# bwrev4.net
KiCad netlist of a schematic drawn in EAGLE
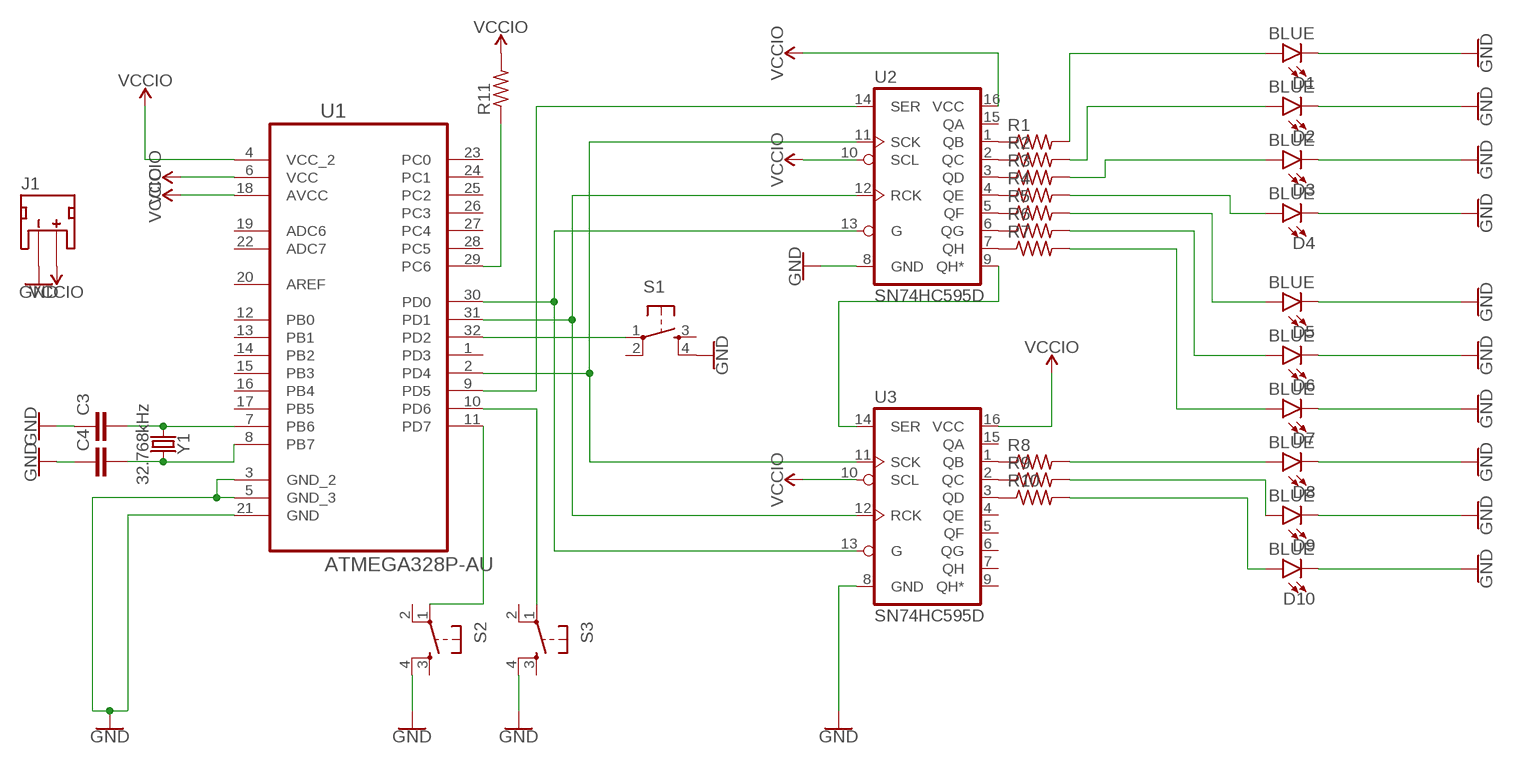
[diagram p0: schematic, sheet 1]

(export (version "E")
  (design (tool "Eeschema 10.0.6"))
  (components
    (comp (ref "C3")
      (value "C-EUC0805")
      (footprint "eagle-import:C0805")
      (libsource (lib "eagle-import") (part "C-EUC0805"))
    )
    (comp (ref "C4")
      (value "C-EUC0805")
      (footprint "eagle-import:C0805")
      (libsource (lib "eagle-import") (part "C-EUC0805"))
    )
    (comp (ref "D1")
      (value "BLUE")
      (footprint "eagle-import:LED-1206")
      (libsource (lib "eagle-import") (part "LED-BLUE1206"))
    )
    (comp (ref "D2")
      (value "BLUE")
      (footprint "eagle-import:LED-1206")
      (libsource (lib "eagle-import") (part "LED-BLUE1206"))
    )
    (comp (ref "D3")
      (value "BLUE")
      (footprint "eagle-import:LED-1206")
      (libsource (lib "eagle-import") (part "LED-BLUE1206"))
    )
    (comp (ref "D4")
      (value "BLUE")
      (footprint "eagle-import:LED-1206")
      (libsource (lib "eagle-import") (part "LED-BLUE1206"))
    )
    (comp (ref "D5")
      (value "BLUE")
      (footprint "eagle-import:LED-1206")
      (libsource (lib "eagle-import") (part "LED-BLUE1206"))
    )
    (comp (ref "D6")
      (value "BLUE")
      (footprint "eagle-import:LED-1206")
      (libsource (lib "eagle-import") (part "LED-BLUE1206"))
    )
    (comp (ref "D7")
      (value "BLUE")
      (footprint "eagle-import:LED-1206")
      (libsource (lib "eagle-import") (part "LED-BLUE1206"))
    )
    (comp (ref "D8")
      (value "BLUE")
      (footprint "eagle-import:LED-1206")
      (libsource (lib "eagle-import") (part "LED-BLUE1206"))
    )
    (comp (ref "D9")
      (value "BLUE")
      (footprint "eagle-import:LED-1206")
      (libsource (lib "eagle-import") (part "LED-BLUE1206"))
    )
    (comp (ref "D10")
      (value "BLUE")
      (footprint "eagle-import:LED-1206")
      (libsource (lib "eagle-import") (part "LED-BLUE1206"))
    )
    (comp (ref "J1")
      (value "JST_2MM_MALE")
      (footprint "eagle-import:JST-2-SMD")
      (libsource (lib "eagle-import") (part "JST_2MM_MALE"))
    )
    (comp (ref "R1")
      (value "R-US_M0805")
      (footprint "eagle-import:M0805")
      (libsource (lib "eagle-import") (part "R-US_M0805"))
    )
    (comp (ref "R2")
      (value "R-US_M0805")
      (footprint "eagle-import:M0805")
      (libsource (lib "eagle-import") (part "R-US_M0805"))
    )
    (comp (ref "R3")
      (value "R-US_M0805")
      (footprint "eagle-import:M0805")
      (libsource (lib "eagle-import") (part "R-US_M0805"))
    )
    (comp (ref "R4")
      (value "R-US_M0805")
      (footprint "eagle-import:M0805")
      (libsource (lib "eagle-import") (part "R-US_M0805"))
    )
    (comp (ref "R5")
      (value "R-US_M0805")
      (footprint "eagle-import:M0805")
      (libsource (lib "eagle-import") (part "R-US_M0805"))
    )
    (comp (ref "R6")
      (value "R-US_M0805")
      (footprint "eagle-import:M0805")
      (libsource (lib "eagle-import") (part "R-US_M0805"))
    )
    (comp (ref "R7")
      (value "R-US_M0805")
      (footprint "eagle-import:M0805")
      (libsource (lib "eagle-import") (part "R-US_M0805"))
    )
    (comp (ref "R8")
      (value "R-US_M0805")
      (footprint "eagle-import:M0805")
      (libsource (lib "eagle-import") (part "R-US_M0805"))
    )
    (comp (ref "R9")
      (value "R-US_M0805")
      (footprint "eagle-import:M0805")
      (libsource (lib "eagle-import") (part "R-US_M0805"))
    )
    (comp (ref "R10")
      (value "R-US_M0805")
      (footprint "eagle-import:M0805")
      (libsource (lib "eagle-import") (part "R-US_M0805"))
    )
    (comp (ref "R11")
      (value "R-US_M0805")
      (footprint "eagle-import:M0805")
      (libsource (lib "eagle-import") (part "R-US_M0805"))
    )
    (comp (ref "S1")
      (value "TAC_SWITCHPTH")
      (footprint "eagle-import:TACTILE-PTH")
      (libsource (lib "eagle-import") (part "TAC_SWITCHPTH"))
    )
    (comp (ref "S2")
      (value "TAC_SWITCHPTH")
      (footprint "eagle-import:TACTILE-PTH")
      (fields (field (name "SPICEPREFIX") "S"))
      (libsource (lib "eagle-import") (part "TAC_SWITCHPTH"))
    )
    (comp (ref "S3")
      (value "TAC_SWITCHPTH")
      (footprint "eagle-import:TACTILE-PTH")
      (libsource (lib "eagle-import") (part "TAC_SWITCHPTH"))
    )
    (comp (ref "U1")
      (value "ATMEGA328P-AU")
      (footprint "eagle-import:QFP80P900X900X120-32N")
      (libsource (lib "eagle-import") (part "ATMEGA328P-AU"))
    )
    (comp (ref "U2")
      (value "SN74HC595D")
      (footprint "eagle-import:SO16")
      (libsource (lib "eagle-import") (part "74595DHC"))
    )
    (comp (ref "U3")
      (value "SN74HC595D")
      (footprint "eagle-import:SO16")
      (libsource (lib "eagle-import") (part "74595DHC"))
    )
    (comp (ref "Y1")
      (value "32.768kHz")
      (footprint "eagle-import:CRYSTAL-SMD-3.2X1.5MM")
      (libsource (lib "eagle-import") (part "CRYSTAL-32.768KHZSMD-3.2X1.5"))
    )
  )
  (nets
    (net (code "1") (name "GND") (class "Default")
      (node (ref "C3") (pin "1") (pinfunction "1_1") (pintype "passive"))
      (node (ref "C4") (pin "1") (pinfunction "1_1") (pintype "passive"))
      (node (ref "D1") (pin "C") (pinfunction "C_C") (pintype "passive"))
      (node (ref "D10") (pin "C") (pinfunction "C_C") (pintype "passive"))
      (node (ref "D2") (pin "C") (pinfunction "C_C") (pintype "passive"))
      (node (ref "D3") (pin "C") (pinfunction "C_C") (pintype "passive"))
      (node (ref "D4") (pin "C") (pinfunction "C_C") (pintype "passive"))
      (node (ref "D5") (pin "C") (pinfunction "C_C") (pintype "passive"))
      (node (ref "D6") (pin "C") (pinfunction "C_C") (pintype "passive"))
      (node (ref "D7") (pin "C") (pinfunction "C_C") (pintype "passive"))
      (node (ref "D8") (pin "C") (pinfunction "C_C") (pintype "passive"))
      (node (ref "D9") (pin "C") (pinfunction "C_C") (pintype "passive"))
      (node (ref "J1") (pin "1") (pinfunction "-_1") (pintype "bidirectional"))
      (node (ref "S1") (pin "4") (pinfunction "4_4") (pintype "passive"))
      (node (ref "S2") (pin "4") (pinfunction "4_4") (pintype "passive"))
      (node (ref "S3") (pin "4") (pinfunction "4_4") (pintype "passive"))
      (node (ref "U1") (pin "21") (pinfunction "GND_21") (pintype "passive"))
      (node (ref "U1") (pin "3") (pinfunction "GND_2_3") (pintype "passive"))
      (node (ref "U1") (pin "5") (pinfunction "GND_3_5") (pintype "passive"))
      (node (ref "U2") (pin "8") (pinfunction "GND_8") (pintype "power_in"))
      (node (ref "U3") (pin "8") (pinfunction "GND_8") (pintype "power_in"))
    )
    (net (code "2") (name "Net-(D1-PadA)") (class "Default")
      (node (ref "D1") (pin "A") (pinfunction "A_A") (pintype "passive"))
      (node (ref "R1") (pin "2") (pinfunction "2_2") (pintype "passive"))
    )
    (net (code "3") (name "Net-(D2-PadA)") (class "Default")
      (node (ref "D2") (pin "A") (pinfunction "A_A") (pintype "passive"))
      (node (ref "R2") (pin "2") (pinfunction "2_2") (pintype "passive"))
    )
    (net (code "4") (name "Net-(D3-PadA)") (class "Default")
      (node (ref "D3") (pin "A") (pinfunction "A_A") (pintype "passive"))
      (node (ref "R3") (pin "2") (pinfunction "2_2") (pintype "passive"))
    )
    (net (code "5") (name "Net-(D4-PadA)") (class "Default")
      (node (ref "D4") (pin "A") (pinfunction "A_A") (pintype "passive"))
      (node (ref "R4") (pin "2") (pinfunction "2_2") (pintype "passive"))
    )
    (net (code "6") (name "Net-(D5-PadA)") (class "Default")
      (node (ref "D5") (pin "A") (pinfunction "A_A") (pintype "passive"))
      (node (ref "R5") (pin "2") (pinfunction "2_2") (pintype "passive"))
    )
    (net (code "7") (name "Net-(D6-PadA)") (class "Default")
      (node (ref "D6") (pin "A") (pinfunction "A_A") (pintype "passive"))
      (node (ref "R6") (pin "2") (pinfunction "2_2") (pintype "passive"))
    )
    (net (code "8") (name "Net-(D7-PadA)") (class "Default")
      (node (ref "D7") (pin "A") (pinfunction "A_A") (pintype "passive"))
      (node (ref "R7") (pin "2") (pinfunction "2_2") (pintype "passive"))
    )
    (net (code "9") (name "Net-(D8-PadA)") (class "Default")
      (node (ref "D8") (pin "A") (pinfunction "A_A") (pintype "passive"))
      (node (ref "R8") (pin "2") (pinfunction "2_2") (pintype "passive"))
    )
    (net (code "10") (name "Net-(D9-PadA)") (class "Default")
      (node (ref "D9") (pin "A") (pinfunction "A_A") (pintype "passive"))
      (node (ref "R9") (pin "2") (pinfunction "2_2") (pintype "passive"))
    )
    (net (code "11") (name "Net-(D10-PadA)") (class "Default")
      (node (ref "D10") (pin "A") (pinfunction "A_A") (pintype "passive"))
      (node (ref "R10") (pin "2") (pinfunction "2_2") (pintype "passive"))
    )
    (net (code "12") (name "Net-(U1-PB6)") (class "Default")
      (node (ref "C3") (pin "2") (pinfunction "2_2") (pintype "passive"))
      (node (ref "U1") (pin "7") (pinfunction "PB6_7") (pintype "bidirectional"))
      (node (ref "Y1") (pin "P$1") (pinfunction "1_P$1") (pintype "passive"))
    )
    (net (code "13") (name "Net-(U1-PB7)") (class "Default")
      (node (ref "C4") (pin "2") (pinfunction "2_2") (pintype "passive"))
      (node (ref "U1") (pin "8") (pinfunction "PB7_8") (pintype "bidirectional"))
      (node (ref "Y1") (pin "P$2") (pinfunction "2_P$2") (pintype "passive"))
    )
    (net (code "14") (name "Net-(U1-PC6)") (class "Default")
      (node (ref "R11") (pin "1") (pinfunction "1_1") (pintype "passive"))
      (node (ref "U1") (pin "29") (pinfunction "PC6_29") (pintype "bidirectional"))
    )
    (net (code "15") (name "Net-(U1-PD0)") (class "Default")
      (node (ref "U1") (pin "30") (pinfunction "PD0_30") (pintype "bidirectional"))
      (node (ref "U2") (pin "13") (pinfunction "G_13") (pintype "input"))
      (node (ref "U3") (pin "13") (pinfunction "G_13") (pintype "input"))
    )
    (net (code "16") (name "Net-(U1-PD1)") (class "Default")
      (node (ref "U1") (pin "31") (pinfunction "PD1_31") (pintype "bidirectional"))
      (node (ref "U2") (pin "12") (pinfunction "RCK_12") (pintype "input"))
      (node (ref "U3") (pin "12") (pinfunction "RCK_12") (pintype "input"))
    )
    (net (code "17") (name "Net-(U1-PD2)") (class "Default")
      (node (ref "S1") (pin "1") (pinfunction "1_1") (pintype "passive"))
      (node (ref "U1") (pin "32") (pinfunction "PD2_32") (pintype "bidirectional"))
    )
    (net (code "18") (name "Net-(U1-PD4)") (class "Default")
      (node (ref "U1") (pin "2") (pinfunction "PD4_2") (pintype "bidirectional"))
      (node (ref "U2") (pin "11") (pinfunction "SCK_11") (pintype "input"))
      (node (ref "U3") (pin "11") (pinfunction "SCK_11") (pintype "input"))
    )
    (net (code "19") (name "Net-(U1-PD5)") (class "Default")
      (node (ref "U1") (pin "9") (pinfunction "PD5_9") (pintype "bidirectional"))
      (node (ref "U2") (pin "14") (pinfunction "SER_14") (pintype "input"))
    )
    (net (code "20") (name "Net-(U1-PD6)") (class "Default")
      (node (ref "S3") (pin "1") (pinfunction "1_1") (pintype "passive"))
      (node (ref "U1") (pin "10") (pinfunction "PD6_10") (pintype "bidirectional"))
    )
    (net (code "21") (name "Net-(U1-PD7)") (class "Default")
      (node (ref "S2") (pin "1") (pinfunction "1_1") (pintype "passive"))
      (node (ref "U1") (pin "11") (pinfunction "PD7_11") (pintype "bidirectional"))
    )
    (net (code "22") (name "Net-(U2-QB)") (class "Default")
      (node (ref "R1") (pin "1") (pinfunction "1_1") (pintype "passive"))
      (node (ref "U2") (pin "1") (pinfunction "QB_1") (pintype "tri_state"))
    )
    (net (code "23") (name "Net-(U2-QC)") (class "Default")
      (node (ref "R2") (pin "1") (pinfunction "1_1") (pintype "passive"))
      (node (ref "U2") (pin "2") (pinfunction "QC_2") (pintype "tri_state"))
    )
    (net (code "24") (name "Net-(U2-QD)") (class "Default")
      (node (ref "R3") (pin "1") (pinfunction "1_1") (pintype "passive"))
      (node (ref "U2") (pin "3") (pinfunction "QD_3") (pintype "tri_state"))
    )
    (net (code "25") (name "Net-(U2-QE)") (class "Default")
      (node (ref "R4") (pin "1") (pinfunction "1_1") (pintype "passive"))
      (node (ref "U2") (pin "4") (pinfunction "QE_4") (pintype "tri_state"))
    )
    (net (code "26") (name "Net-(U2-QF)") (class "Default")
      (node (ref "R5") (pin "1") (pinfunction "1_1") (pintype "passive"))
      (node (ref "U2") (pin "5") (pinfunction "QF_5") (pintype "tri_state"))
    )
    (net (code "27") (name "Net-(U2-QG)") (class "Default")
      (node (ref "R6") (pin "1") (pinfunction "1_1") (pintype "passive"))
      (node (ref "U2") (pin "6") (pinfunction "QG_6") (pintype "tri_state"))
    )
    (net (code "28") (name "Net-(U2-QH)") (class "Default")
      (node (ref "R7") (pin "1") (pinfunction "1_1") (pintype "passive"))
      (node (ref "U2") (pin "7") (pinfunction "QH_7") (pintype "tri_state"))
    )
    (net (code "29") (name "Net-(U2-QH*)") (class "Default")
      (node (ref "U2") (pin "9") (pinfunction "QH*_9") (pintype "tri_state"))
      (node (ref "U3") (pin "14") (pinfunction "SER_14") (pintype "input"))
    )
    (net (code "30") (name "Net-(U3-QB)") (class "Default")
      (node (ref "R8") (pin "1") (pinfunction "1_1") (pintype "passive"))
      (node (ref "U3") (pin "1") (pinfunction "QB_1") (pintype "tri_state"))
    )
    (net (code "31") (name "Net-(U3-QC)") (class "Default")
      (node (ref "R9") (pin "1") (pinfunction "1_1") (pintype "passive"))
      (node (ref "U3") (pin "2") (pinfunction "QC_2") (pintype "tri_state"))
    )
    (net (code "32") (name "Net-(U3-QD)") (class "Default")
      (node (ref "R10") (pin "1") (pinfunction "1_1") (pintype "passive"))
      (node (ref "U3") (pin "3") (pinfunction "QD_3") (pintype "tri_state"))
    )
    (net (code "33") (name "VCCIO") (class "Default")
      (node (ref "J1") (pin "2") (pinfunction "+_2") (pintype "bidirectional"))
      (node (ref "R11") (pin "2") (pinfunction "2_2") (pintype "passive"))
      (node (ref "U1") (pin "18") (pinfunction "AVCC_18") (pintype "power_in"))
      (node (ref "U1") (pin "4") (pinfunction "VCC_2_4") (pintype "power_in"))
      (node (ref "U1") (pin "6") (pinfunction "VCC_6") (pintype "power_in"))
      (node (ref "U2") (pin "10") (pinfunction "SCL_10") (pintype "input"))
      (node (ref "U2") (pin "16") (pinfunction "VCC_16") (pintype "power_in"))
      (node (ref "U3") (pin "10") (pinfunction "SCL_10") (pintype "input"))
      (node (ref "U3") (pin "16") (pinfunction "VCC_16") (pintype "power_in"))
    )
    (net (code "34") (name "unconnected-(J1-PAD1-PadNC1)") (class "Default")
      (node (ref "J1") (pin "NC1") (pinfunction "PAD1_NC1") (pintype "bidirectional"))
    )
    (net (code "35") (name "unconnected-(J1-PAD2-PadNC2)") (class "Default")
      (node (ref "J1") (pin "NC2") (pinfunction "PAD2_NC2") (pintype "bidirectional"))
    )
    (net (code "36") (name "unconnected-(S1-Pad2)") (class "Default")
      (node (ref "S1") (pin "2") (pinfunction "2_2") (pintype "passive"))
    )
    (net (code "37") (name "unconnected-(S1-Pad3)") (class "Default")
      (node (ref "S1") (pin "3") (pinfunction "3_3") (pintype "passive"))
    )
    (net (code "38") (name "unconnected-(S2-Pad2)") (class "Default")
      (node (ref "S2") (pin "2") (pinfunction "2_2") (pintype "passive"))
    )
    (net (code "39") (name "unconnected-(S2-Pad3)") (class "Default")
      (node (ref "S2") (pin "3") (pinfunction "3_3") (pintype "passive"))
    )
    (net (code "40") (name "unconnected-(S3-Pad2)") (class "Default")
      (node (ref "S3") (pin "2") (pinfunction "2_2") (pintype "passive"))
    )
    (net (code "41") (name "unconnected-(S3-Pad3)") (class "Default")
      (node (ref "S3") (pin "3") (pinfunction "3_3") (pintype "passive"))
    )
    (net (code "42") (name "unconnected-(U1-ADC6-Pad19)") (class "Default")
      (node (ref "U1") (pin "19") (pinfunction "ADC6_19") (pintype "input"))
    )
    (net (code "43") (name "unconnected-(U1-ADC7-Pad22)") (class "Default")
      (node (ref "U1") (pin "22") (pinfunction "ADC7_22") (pintype "input"))
    )
    (net (code "44") (name "unconnected-(U1-AREF-Pad20)") (class "Default")
      (node (ref "U1") (pin "20") (pinfunction "AREF_20") (pintype "input"))
    )
    (net (code "45") (name "unconnected-(U1-PB0-Pad12)") (class "Default")
      (node (ref "U1") (pin "12") (pinfunction "PB0_12") (pintype "bidirectional"))
    )
    (net (code "46") (name "unconnected-(U1-PB1-Pad13)") (class "Default")
      (node (ref "U1") (pin "13") (pinfunction "PB1_13") (pintype "bidirectional"))
    )
    (net (code "47") (name "unconnected-(U1-PB2-Pad14)") (class "Default")
      (node (ref "U1") (pin "14") (pinfunction "PB2_14") (pintype "bidirectional"))
    )
    (net (code "48") (name "unconnected-(U1-PB3-Pad15)") (class "Default")
      (node (ref "U1") (pin "15") (pinfunction "PB3_15") (pintype "bidirectional"))
    )
    (net (code "49") (name "unconnected-(U1-PB4-Pad16)") (class "Default")
      (node (ref "U1") (pin "16") (pinfunction "PB4_16") (pintype "bidirectional"))
    )
    (net (code "50") (name "unconnected-(U1-PB5-Pad17)") (class "Default")
      (node (ref "U1") (pin "17") (pinfunction "PB5_17") (pintype "bidirectional"))
    )
    (net (code "51") (name "unconnected-(U1-PC0-Pad23)") (class "Default")
      (node (ref "U1") (pin "23") (pinfunction "PC0_23") (pintype "bidirectional"))
    )
    (net (code "52") (name "unconnected-(U1-PC1-Pad24)") (class "Default")
      (node (ref "U1") (pin "24") (pinfunction "PC1_24") (pintype "bidirectional"))
    )
    (net (code "53") (name "unconnected-(U1-PC2-Pad25)") (class "Default")
      (node (ref "U1") (pin "25") (pinfunction "PC2_25") (pintype "bidirectional"))
    )
    (net (code "54") (name "unconnected-(U1-PC3-Pad26)") (class "Default")
      (node (ref "U1") (pin "26") (pinfunction "PC3_26") (pintype "bidirectional"))
    )
    (net (code "55") (name "unconnected-(U1-PC4-Pad27)") (class "Default")
      (node (ref "U1") (pin "27") (pinfunction "PC4_27") (pintype "bidirectional"))
    )
    (net (code "56") (name "unconnected-(U1-PC5-Pad28)") (class "Default")
      (node (ref "U1") (pin "28") (pinfunction "PC5_28") (pintype "bidirectional"))
    )
    (net (code "57") (name "unconnected-(U1-PD3-Pad1)") (class "Default")
      (node (ref "U1") (pin "1") (pinfunction "PD3_1") (pintype "bidirectional"))
    )
    (net (code "58") (name "unconnected-(U2-QA-Pad15)") (class "Default")
      (node (ref "U2") (pin "15") (pinfunction "QA_15") (pintype "tri_state"))
    )
    (net (code "59") (name "unconnected-(U3-QA-Pad15)") (class "Default")
      (node (ref "U3") (pin "15") (pinfunction "QA_15") (pintype "tri_state"))
    )
    (net (code "60") (name "unconnected-(U3-QE-Pad4)") (class "Default")
      (node (ref "U3") (pin "4") (pinfunction "QE_4") (pintype "tri_state"))
    )
    (net (code "61") (name "unconnected-(U3-QF-Pad5)") (class "Default")
      (node (ref "U3") (pin "5") (pinfunction "QF_5") (pintype "tri_state"))
    )
    (net (code "62") (name "unconnected-(U3-QG-Pad6)") (class "Default")
      (node (ref "U3") (pin "6") (pinfunction "QG_6") (pintype "tri_state"))
    )
    (net (code "63") (name "unconnected-(U3-QH*-Pad9)") (class "Default")
      (node (ref "U3") (pin "9") (pinfunction "QH*_9") (pintype "tri_state"))
    )
    (net (code "64") (name "unconnected-(U3-QH-Pad7)") (class "Default")
      (node (ref "U3") (pin "7") (pinfunction "QH_7") (pintype "tri_state"))
    )
  )
)
